# E180-ZG120B-TB-SCH.net
KiCad netlist of a schematic drawn in Altium Designer
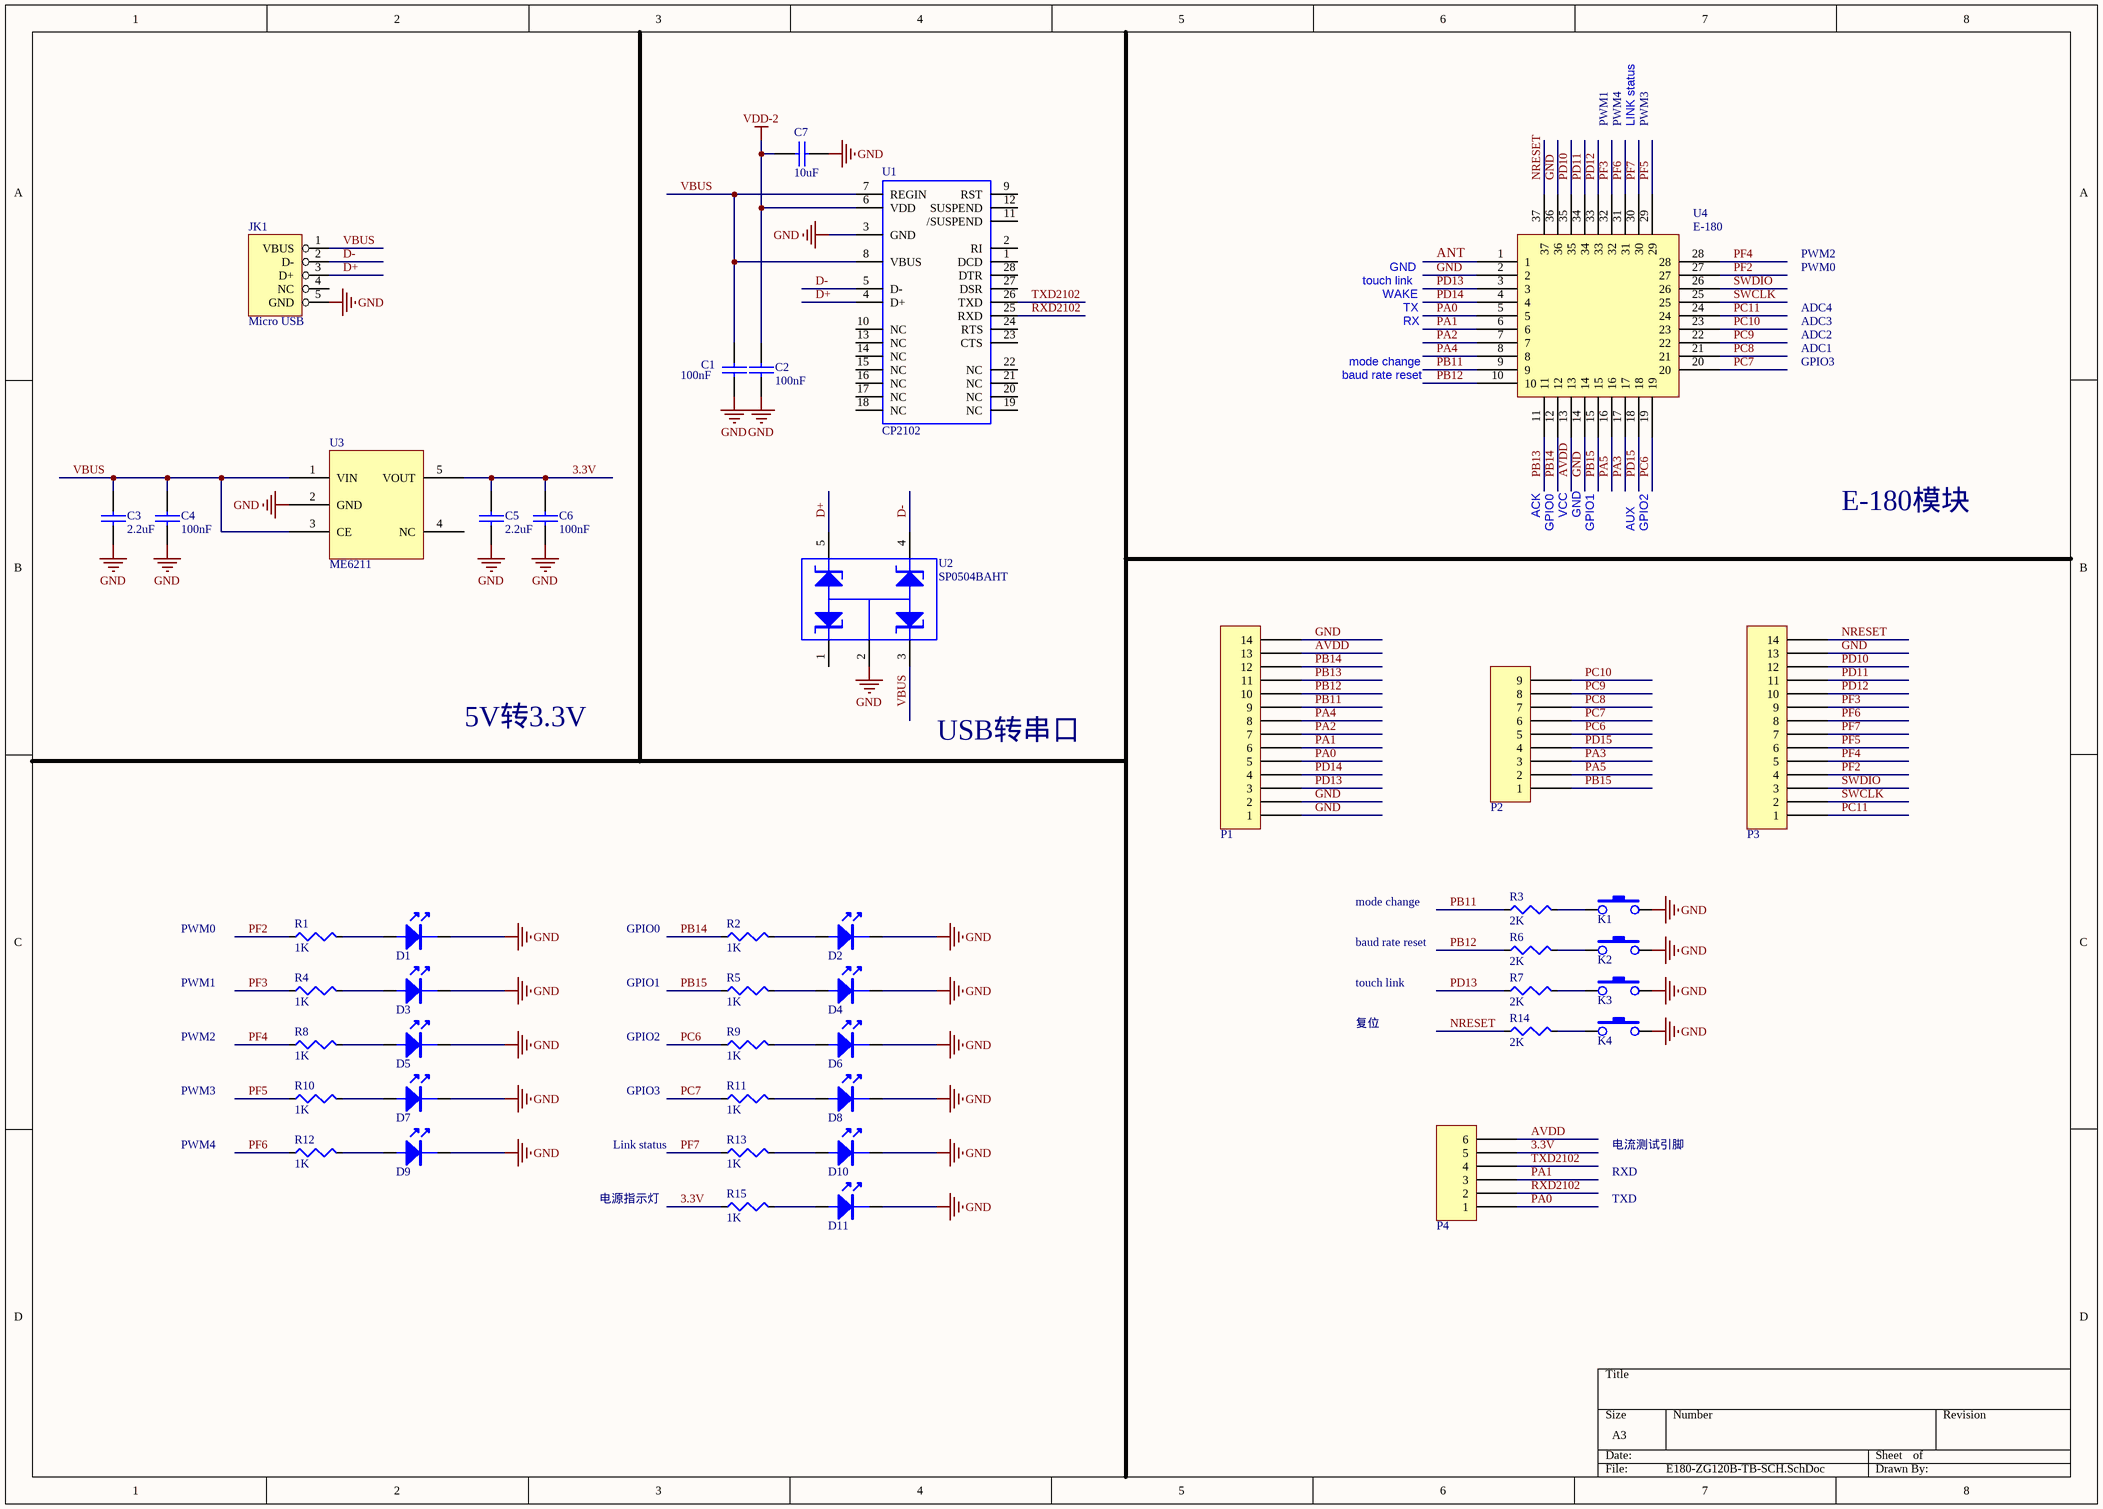
[diagram p0: E180-ZG120B-TB-SCH.SchDoc]

(export (version "E")
  (design (tool "Eeschema 10.0.6"))
  (components
    (comp (ref "C1")
      (value "100nF")
      (footprint "E-CAP-0603")
      (description "Capacitor")
      (libsource (lib "E180-TBB01") (part "CAP 0603"))
    )
    (comp (ref "C2")
      (value "100nF")
      (footprint "E-CAP-0603")
      (description "Capacitor")
      (libsource (lib "E180-TBB01") (part "CAP 0603"))
    )
    (comp (ref "C3")
      (value "2.2uF")
      (footprint "E-CAP-0603")
      (description "Capacitor")
      (libsource (lib "E180-TBB01") (part "CAP 0603"))
    )
    (comp (ref "C4")
      (value "100nF")
      (footprint "E-CAP-0603")
      (description "Capacitor")
      (libsource (lib "E180-TBB01") (part "CAP 0603"))
    )
    (comp (ref "C5")
      (value "2.2uF")
      (footprint "E-CAP-0603")
      (description "Capacitor")
      (libsource (lib "E180-TBB01") (part "CAP 0603"))
    )
    (comp (ref "C6")
      (value "100nF")
      (footprint "E-CAP-0603")
      (description "Capacitor")
      (libsource (lib "E180-TBB01") (part "CAP 0603"))
    )
    (comp (ref "C7")
      (value "10uF")
      (footprint "E-CAP-0603")
      (description "Capacitor")
      (libsource (lib "E180-TBB01") (part "CAP 0603"))
    )
    (comp (ref "D1") (value "LED") (footprint "E-LED-0603") (libsource (lib "E180-TBB01") (part "LED")))
    (comp (ref "D2") (value "LED") (footprint "E-LED-0603") (libsource (lib "E180-TBB01") (part "LED")))
    (comp (ref "D3") (value "LED") (footprint "E-LED-0603") (libsource (lib "E180-TBB01") (part "LED")))
    (comp (ref "D4") (value "LED") (footprint "E-LED-0603") (libsource (lib "E180-TBB01") (part "LED")))
    (comp (ref "D5") (value "LED") (footprint "E-LED-0603") (libsource (lib "E180-TBB01") (part "LED")))
    (comp (ref "D6") (value "LED") (footprint "E-LED-0603") (libsource (lib "E180-TBB01") (part "LED")))
    (comp (ref "D7") (value "LED") (footprint "E-LED-0603") (libsource (lib "E180-TBB01") (part "LED")))
    (comp (ref "D8") (value "LED") (footprint "E-LED-0603") (libsource (lib "E180-TBB01") (part "LED")))
    (comp (ref "D9") (value "LED") (footprint "E-LED-0603") (libsource (lib "E180-TBB01") (part "LED")))
    (comp (ref "D10") (value "LED") (footprint "E-LED-0603") (libsource (lib "E180-TBB01") (part "LED")))
    (comp (ref "D11") (value "LED") (footprint "E-LED-0603") (libsource (lib "E180-TBB01") (part "LED")))
    (comp (ref "JK1")
      (value "Micro USB")
      (footprint "E-Micro USB-5SB")
      (libsource (lib "E180-TBB01") (part "Micro USB"))
    )
    (comp (ref "K1") (value "KEY0") (footprint "KEY") (libsource (lib "E180-TBB01") (part "KEY0")))
    (comp (ref "K2") (value "KEY0") (footprint "KEY") (libsource (lib "E180-TBB01") (part "KEY0")))
    (comp (ref "K3") (value "KEY0") (footprint "KEY") (libsource (lib "E180-TBB01") (part "KEY0")))
    (comp (ref "K4") (value "KEY0") (footprint "KEY") (libsource (lib "E180-TBB01") (part "KEY0")))
    (comp (ref "P1")
      (value "Header1*14")
      (footprint "E-2X7P-2.54-1")
      (libsource (lib "E180-TBB01") (part "Header1*14"))
    )
    (comp (ref "P2")
      (value "Header1*9")
      (footprint "E-9P-2.54-1")
      (libsource (lib "E180-TBB01") (part "Header1*9"))
    )
    (comp (ref "P3")
      (value "Header1*14")
      (footprint "E-2X7P-2.54-1")
      (libsource (lib "E180-TBB01") (part "Header1*14"))
    )
    (comp (ref "P4")
      (value "Header1*6")
      (footprint "E-6P-2.54-1")
      (libsource (lib "E180-TBB01") (part "Header1*6"))
    )
    (comp (ref "R1") (value "1K") (footprint "E-RES-0603") (libsource (lib "E180-TBB01") (part "RES 0603")))
    (comp (ref "R2") (value "1K") (footprint "E-RES-0603") (libsource (lib "E180-TBB01") (part "RES 0603")))
    (comp (ref "R3") (value "2K") (footprint "E-RES-0603") (libsource (lib "E180-TBB01") (part "RES 0603")))
    (comp (ref "R4") (value "1K") (footprint "E-RES-0603") (libsource (lib "E180-TBB01") (part "RES 0603")))
    (comp (ref "R5") (value "1K") (footprint "E-RES-0603") (libsource (lib "E180-TBB01") (part "RES 0603")))
    (comp (ref "R6") (value "2K") (footprint "E-RES-0603") (libsource (lib "E180-TBB01") (part "RES 0603")))
    (comp (ref "R7") (value "2K") (footprint "E-RES-0603") (libsource (lib "E180-TBB01") (part "RES 0603")))
    (comp (ref "R8") (value "1K") (footprint "E-RES-0603") (libsource (lib "E180-TBB01") (part "RES 0603")))
    (comp (ref "R9") (value "1K") (footprint "E-RES-0603") (libsource (lib "E180-TBB01") (part "RES 0603")))
    (comp (ref "R10") (value "1K") (footprint "E-RES-0603") (libsource (lib "E180-TBB01") (part "RES 0603")))
    (comp (ref "R11") (value "1K") (footprint "E-RES-0603") (libsource (lib "E180-TBB01") (part "RES 0603")))
    (comp (ref "R12") (value "1K") (footprint "E-RES-0603") (libsource (lib "E180-TBB01") (part "RES 0603")))
    (comp (ref "R13") (value "1K") (footprint "E-RES-0603") (libsource (lib "E180-TBB01") (part "RES 0603")))
    (comp (ref "R14") (value "2K") (footprint "E-RES-0603") (libsource (lib "E180-TBB01") (part "RES 0603")))
    (comp (ref "R15") (value "1K") (footprint "E-RES-0603") (libsource (lib "E180-TBB01") (part "RES 0603")))
    (comp (ref "U1")
      (value "CP2102")
      (footprint "E-QFN28-5X5-P0.5")
      (libsource (lib "E180-TBB01") (part "CP2102"))
    )
    (comp (ref "U2") (value "SP0504BAHT") (footprint "SP0504") (libsource (lib "E180-TBB01") (part "SP0504")))
    (comp (ref "U3") (value "ME6211") (footprint "E-SOT23-5") (libsource (lib "E180-TBB01") (part "HT7233")))
    (comp (ref "U4") (value "E-180") (footprint "E-180") (libsource (lib "E180-TBB01") (part "E-180")))
  )
  (nets
    (net (code "1") (name "/3.3V") (class "Default")
      (node (ref "C5") (pin "1") (pinfunction "1_1") (pintype "passive"))
      (node (ref "C6") (pin "1") (pinfunction "1_1") (pintype "passive"))
      (node (ref "P4") (pin "5") (pinfunction "5_5") (pintype "passive"))
      (node (ref "R15") (pin "1") (pinfunction "1_1") (pintype "passive"))
      (node (ref "U3") (pin "5") (pinfunction "VOUT_5") (pintype "passive"))
    )
    (net (code "3") (name "/ANT") (class "Default")
      (node (ref "U4") (pin "1") (pinfunction "1_1") (pintype "passive"))
    )
    (net (code "5") (name "/AVDD") (class "Default")
      (node (ref "P1") (pin "13") (pinfunction "13_13") (pintype "passive"))
      (node (ref "P4") (pin "6") (pinfunction "6_6") (pintype "passive"))
      (node (ref "U4") (pin "13") (pinfunction "13_13") (pintype "passive"))
    )
    (net (code "6") (name "/D+") (class "Default")
      (node (ref "JK1") (pin "3") (pinfunction "D+_3") (pintype "passive"))
      (node (ref "U1") (pin "4") (pinfunction "D+_4") (pintype "passive"))
      (node (ref "U2") (pin "5") (pinfunction "5_5") (pintype "passive"))
    )
    (net (code "7") (name "/D-") (class "Default")
      (node (ref "JK1") (pin "2") (pinfunction "D-_2") (pintype "passive"))
      (node (ref "U1") (pin "5") (pinfunction "D-_5") (pintype "passive"))
      (node (ref "U2") (pin "4") (pinfunction "4_4") (pintype "passive"))
    )
    (net (code "12") (name "/NRESET") (class "Default")
      (node (ref "P3") (pin "14") (pinfunction "14_14") (pintype "passive"))
      (node (ref "R14") (pin "1") (pinfunction "1_1") (pintype "passive"))
      (node (ref "U4") (pin "37") (pinfunction "37_37") (pintype "passive"))
    )
    (net (code "13") (name "/PA0") (class "Default")
      (node (ref "P1") (pin "5") (pinfunction "5_5") (pintype "passive"))
      (node (ref "P4") (pin "1") (pinfunction "1_1") (pintype "passive"))
      (node (ref "U4") (pin "5") (pinfunction "5_5") (pintype "passive"))
    )
    (net (code "14") (name "/PA1") (class "Default")
      (node (ref "P1") (pin "6") (pinfunction "6_6") (pintype "passive"))
      (node (ref "P4") (pin "3") (pinfunction "3_3") (pintype "passive"))
      (node (ref "U4") (pin "6") (pinfunction "6_6") (pintype "passive"))
    )
    (net (code "15") (name "/PA2") (class "Default")
      (node (ref "P1") (pin "7") (pinfunction "7_7") (pintype "passive"))
      (node (ref "U4") (pin "7") (pinfunction "7_7") (pintype "passive"))
    )
    (net (code "16") (name "/PA3") (class "Default")
      (node (ref "P2") (pin "3") (pinfunction "3_3") (pintype "passive"))
      (node (ref "U4") (pin "17") (pinfunction "17_17") (pintype "passive"))
    )
    (net (code "17") (name "/PA4") (class "Default")
      (node (ref "P1") (pin "8") (pinfunction "8_8") (pintype "passive"))
      (node (ref "U4") (pin "8") (pinfunction "8_8") (pintype "passive"))
    )
    (net (code "18") (name "/PA5") (class "Default")
      (node (ref "P2") (pin "2") (pinfunction "2_2") (pintype "passive"))
      (node (ref "U4") (pin "16") (pinfunction "16_16") (pintype "passive"))
    )
    (net (code "19") (name "/PB11") (class "Default")
      (node (ref "P1") (pin "9") (pinfunction "9_9") (pintype "passive"))
      (node (ref "R3") (pin "1") (pinfunction "1_1") (pintype "passive"))
      (node (ref "U4") (pin "9") (pinfunction "9_9") (pintype "passive"))
    )
    (net (code "20") (name "/PB12") (class "Default")
      (node (ref "P1") (pin "10") (pinfunction "10_10") (pintype "passive"))
      (node (ref "R6") (pin "1") (pinfunction "1_1") (pintype "passive"))
      (node (ref "U4") (pin "10") (pinfunction "10_10") (pintype "passive"))
    )
    (net (code "21") (name "/PB13") (class "Default")
      (node (ref "P1") (pin "11") (pinfunction "11_11") (pintype "passive"))
      (node (ref "U4") (pin "11") (pinfunction "11_11") (pintype "passive"))
    )
    (net (code "22") (name "/PB14") (class "Default")
      (node (ref "P1") (pin "12") (pinfunction "12_12") (pintype "passive"))
      (node (ref "R2") (pin "1") (pinfunction "1_1") (pintype "passive"))
      (node (ref "U4") (pin "12") (pinfunction "12_12") (pintype "passive"))
    )
    (net (code "23") (name "/PB15") (class "Default")
      (node (ref "P2") (pin "1") (pinfunction "1_1") (pintype "passive"))
      (node (ref "R5") (pin "1") (pinfunction "1_1") (pintype "passive"))
      (node (ref "U4") (pin "15") (pinfunction "15_15") (pintype "passive"))
    )
    (net (code "24") (name "/PC6") (class "Default")
      (node (ref "P2") (pin "5") (pinfunction "5_5") (pintype "passive"))
      (node (ref "R9") (pin "1") (pinfunction "1_1") (pintype "passive"))
      (node (ref "U4") (pin "19") (pinfunction "19_19") (pintype "passive"))
    )
    (net (code "25") (name "/PC7") (class "Default")
      (node (ref "P2") (pin "6") (pinfunction "6_6") (pintype "passive"))
      (node (ref "R11") (pin "1") (pinfunction "1_1") (pintype "passive"))
      (node (ref "U4") (pin "20") (pinfunction "20_20") (pintype "passive"))
    )
    (net (code "26") (name "/PC8") (class "Default")
      (node (ref "P2") (pin "7") (pinfunction "7_7") (pintype "passive"))
      (node (ref "U4") (pin "21") (pinfunction "21_21") (pintype "passive"))
    )
    (net (code "27") (name "/PC9") (class "Default")
      (node (ref "P2") (pin "8") (pinfunction "8_8") (pintype "passive"))
      (node (ref "U4") (pin "22") (pinfunction "22_22") (pintype "passive"))
    )
    (net (code "28") (name "/PC10") (class "Default")
      (node (ref "P2") (pin "9") (pinfunction "9_9") (pintype "passive"))
      (node (ref "U4") (pin "23") (pinfunction "23_23") (pintype "passive"))
    )
    (net (code "29") (name "/PC11") (class "Default")
      (node (ref "P3") (pin "1") (pinfunction "1_1") (pintype "passive"))
      (node (ref "U4") (pin "24") (pinfunction "24_24") (pintype "passive"))
    )
    (net (code "30") (name "/PD10") (class "Default")
      (node (ref "P3") (pin "12") (pinfunction "12_12") (pintype "passive"))
      (node (ref "U4") (pin "35") (pinfunction "35_35") (pintype "passive"))
    )
    (net (code "31") (name "/PD11") (class "Default")
      (node (ref "P3") (pin "11") (pinfunction "11_11") (pintype "passive"))
      (node (ref "U4") (pin "34") (pinfunction "34_34") (pintype "passive"))
    )
    (net (code "32") (name "/PD12") (class "Default")
      (node (ref "P3") (pin "10") (pinfunction "10_10") (pintype "passive"))
      (node (ref "U4") (pin "33") (pinfunction "33_33") (pintype "passive"))
    )
    (net (code "33") (name "/PD13") (class "Default")
      (node (ref "P1") (pin "3") (pinfunction "3_3") (pintype "passive"))
      (node (ref "R7") (pin "1") (pinfunction "1_1") (pintype "passive"))
      (node (ref "U4") (pin "3") (pinfunction "3_3") (pintype "passive"))
    )
    (net (code "34") (name "/PD14") (class "Default")
      (node (ref "P1") (pin "4") (pinfunction "4_4") (pintype "passive"))
      (node (ref "U4") (pin "4") (pinfunction "4_4") (pintype "passive"))
    )
    (net (code "35") (name "/PD15") (class "Default")
      (node (ref "P2") (pin "4") (pinfunction "4_4") (pintype "passive"))
      (node (ref "U4") (pin "18") (pinfunction "18_18") (pintype "passive"))
    )
    (net (code "36") (name "/PF2") (class "Default")
      (node (ref "P3") (pin "4") (pinfunction "4_4") (pintype "passive"))
      (node (ref "R1") (pin "1") (pinfunction "1_1") (pintype "passive"))
      (node (ref "U4") (pin "27") (pinfunction "27_27") (pintype "passive"))
    )
    (net (code "37") (name "/PF3") (class "Default")
      (node (ref "P3") (pin "9") (pinfunction "9_9") (pintype "passive"))
      (node (ref "R4") (pin "1") (pinfunction "1_1") (pintype "passive"))
      (node (ref "U4") (pin "32") (pinfunction "32_32") (pintype "passive"))
    )
    (net (code "38") (name "/PF4") (class "Default")
      (node (ref "P3") (pin "5") (pinfunction "5_5") (pintype "passive"))
      (node (ref "R8") (pin "1") (pinfunction "1_1") (pintype "passive"))
      (node (ref "U4") (pin "28") (pinfunction "28_28") (pintype "passive"))
    )
    (net (code "39") (name "/PF5") (class "Default")
      (node (ref "P3") (pin "6") (pinfunction "6_6") (pintype "passive"))
      (node (ref "R10") (pin "1") (pinfunction "1_1") (pintype "passive"))
      (node (ref "U4") (pin "29") (pinfunction "29_29") (pintype "passive"))
    )
    (net (code "40") (name "/PF6") (class "Default")
      (node (ref "P3") (pin "8") (pinfunction "8_8") (pintype "passive"))
      (node (ref "R12") (pin "1") (pinfunction "1_1") (pintype "passive"))
      (node (ref "U4") (pin "31") (pinfunction "31_31") (pintype "passive"))
    )
    (net (code "41") (name "/PF7") (class "Default")
      (node (ref "P3") (pin "7") (pinfunction "7_7") (pintype "passive"))
      (node (ref "R13") (pin "1") (pinfunction "1_1") (pintype "passive"))
      (node (ref "U4") (pin "30") (pinfunction "30_30") (pintype "passive"))
    )
    (net (code "43") (name "/RXD2102") (class "Default")
      (node (ref "P4") (pin "2") (pinfunction "2_2") (pintype "passive"))
      (node (ref "U1") (pin "25") (pinfunction "RXD_25") (pintype "passive"))
    )
    (net (code "44") (name "/SWCLK") (class "Default")
      (node (ref "P3") (pin "2") (pinfunction "2_2") (pintype "passive"))
      (node (ref "U4") (pin "25") (pinfunction "25_25") (pintype "passive"))
    )
    (net (code "45") (name "/SWDIO") (class "Default")
      (node (ref "P3") (pin "3") (pinfunction "3_3") (pintype "passive"))
      (node (ref "U4") (pin "26") (pinfunction "26_26") (pintype "passive"))
    )
    (net (code "47") (name "/TXD2102") (class "Default")
      (node (ref "P4") (pin "4") (pinfunction "4_4") (pintype "passive"))
      (node (ref "U1") (pin "26") (pinfunction "TXD_26") (pintype "passive"))
    )
    (net (code "48") (name "/VBUS") (class "Default")
      (node (ref "C1") (pin "1") (pinfunction "1_1") (pintype "passive"))
      (node (ref "C3") (pin "1") (pinfunction "1_1") (pintype "passive"))
      (node (ref "C4") (pin "1") (pinfunction "1_1") (pintype "passive"))
      (node (ref "JK1") (pin "1") (pinfunction "VBUS_1") (pintype "passive"))
      (node (ref "U1") (pin "7") (pinfunction "REGIN_7") (pintype "passive"))
      (node (ref "U1") (pin "8") (pinfunction "VBUS_8") (pintype "passive"))
      (node (ref "U2") (pin "3") (pinfunction "3_3") (pintype "passive"))
      (node (ref "U3") (pin "1") (pinfunction "VIN_1") (pintype "passive"))
      (node (ref "U3") (pin "3") (pinfunction "CE_3") (pintype "passive"))
    )
    (net (code "54") (name "GND") (class "Default")
      (node (ref "C1") (pin "2") (pinfunction "2_2") (pintype "passive"))
      (node (ref "C2") (pin "2") (pinfunction "2_2") (pintype "passive"))
      (node (ref "C3") (pin "2") (pinfunction "2_2") (pintype "passive"))
      (node (ref "C4") (pin "2") (pinfunction "2_2") (pintype "passive"))
      (node (ref "C5") (pin "2") (pinfunction "2_2") (pintype "passive"))
      (node (ref "C6") (pin "2") (pinfunction "2_2") (pintype "passive"))
      (node (ref "C7") (pin "2") (pinfunction "2_2") (pintype "passive"))
      (node (ref "D1") (pin "K") (pinfunction "K_K") (pintype "passive"))
      (node (ref "D10") (pin "K") (pinfunction "K_K") (pintype "passive"))
      (node (ref "D11") (pin "K") (pinfunction "K_K") (pintype "passive"))
      (node (ref "D2") (pin "K") (pinfunction "K_K") (pintype "passive"))
      (node (ref "D3") (pin "K") (pinfunction "K_K") (pintype "passive"))
      (node (ref "D4") (pin "K") (pinfunction "K_K") (pintype "passive"))
      (node (ref "D5") (pin "K") (pinfunction "K_K") (pintype "passive"))
      (node (ref "D6") (pin "K") (pinfunction "K_K") (pintype "passive"))
      (node (ref "D7") (pin "K") (pinfunction "K_K") (pintype "passive"))
      (node (ref "D8") (pin "K") (pinfunction "K_K") (pintype "passive"))
      (node (ref "D9") (pin "K") (pinfunction "K_K") (pintype "passive"))
      (node (ref "JK1") (pin "5") (pinfunction "GND_5") (pintype "passive"))
      (node (ref "K1") (pin "2") (pinfunction "2_2") (pintype "passive"))
      (node (ref "K2") (pin "2") (pinfunction "2_2") (pintype "passive"))
      (node (ref "K3") (pin "2") (pinfunction "2_2") (pintype "passive"))
      (node (ref "K4") (pin "2") (pinfunction "2_2") (pintype "passive"))
      (node (ref "P1") (pin "1") (pinfunction "1_1") (pintype "passive"))
      (node (ref "P1") (pin "14") (pinfunction "14_14") (pintype "passive"))
      (node (ref "P1") (pin "2") (pinfunction "2_2") (pintype "passive"))
      (node (ref "P3") (pin "13") (pinfunction "13_13") (pintype "passive"))
      (node (ref "U1") (pin "3") (pinfunction "GND_3") (pintype "passive"))
      (node (ref "U2") (pin "2") (pinfunction "2_2") (pintype "passive"))
      (node (ref "U3") (pin "2") (pinfunction "GND_2") (pintype "passive"))
      (node (ref "U4") (pin "14") (pinfunction "14_14") (pintype "passive"))
      (node (ref "U4") (pin "2") (pinfunction "2_2") (pintype "passive"))
      (node (ref "U4") (pin "36") (pinfunction "36_36") (pintype "passive"))
    )
    (net (code "55") (name "Net-(D1-PadA)") (class "Default")
      (node (ref "D1") (pin "A") (pinfunction "A_A") (pintype "passive"))
      (node (ref "R1") (pin "2") (pinfunction "2_2") (pintype "passive"))
    )
    (net (code "56") (name "Net-(D2-PadA)") (class "Default")
      (node (ref "D2") (pin "A") (pinfunction "A_A") (pintype "passive"))
      (node (ref "R2") (pin "2") (pinfunction "2_2") (pintype "passive"))
    )
    (net (code "57") (name "Net-(D3-PadA)") (class "Default")
      (node (ref "D3") (pin "A") (pinfunction "A_A") (pintype "passive"))
      (node (ref "R4") (pin "2") (pinfunction "2_2") (pintype "passive"))
    )
    (net (code "58") (name "Net-(D4-PadA)") (class "Default")
      (node (ref "D4") (pin "A") (pinfunction "A_A") (pintype "passive"))
      (node (ref "R5") (pin "2") (pinfunction "2_2") (pintype "passive"))
    )
    (net (code "59") (name "Net-(D5-PadA)") (class "Default")
      (node (ref "D5") (pin "A") (pinfunction "A_A") (pintype "passive"))
      (node (ref "R8") (pin "2") (pinfunction "2_2") (pintype "passive"))
    )
    (net (code "60") (name "Net-(D6-PadA)") (class "Default")
      (node (ref "D6") (pin "A") (pinfunction "A_A") (pintype "passive"))
      (node (ref "R9") (pin "2") (pinfunction "2_2") (pintype "passive"))
    )
    (net (code "61") (name "Net-(D7-PadA)") (class "Default")
      (node (ref "D7") (pin "A") (pinfunction "A_A") (pintype "passive"))
      (node (ref "R10") (pin "2") (pinfunction "2_2") (pintype "passive"))
    )
    (net (code "62") (name "Net-(D8-PadA)") (class "Default")
      (node (ref "D8") (pin "A") (pinfunction "A_A") (pintype "passive"))
      (node (ref "R11") (pin "2") (pinfunction "2_2") (pintype "passive"))
    )
    (net (code "63") (name "Net-(D9-PadA)") (class "Default")
      (node (ref "D9") (pin "A") (pinfunction "A_A") (pintype "passive"))
      (node (ref "R12") (pin "2") (pinfunction "2_2") (pintype "passive"))
    )
    (net (code "64") (name "Net-(D10-PadA)") (class "Default")
      (node (ref "D10") (pin "A") (pinfunction "A_A") (pintype "passive"))
      (node (ref "R13") (pin "2") (pinfunction "2_2") (pintype "passive"))
    )
    (net (code "65") (name "Net-(D11-PadA)") (class "Default")
      (node (ref "D11") (pin "A") (pinfunction "A_A") (pintype "passive"))
      (node (ref "R15") (pin "2") (pinfunction "2_2") (pintype "passive"))
    )
    (net (code "66") (name "Net-(K1-Pad1)") (class "Default")
      (node (ref "K1") (pin "1") (pinfunction "1_1") (pintype "passive"))
      (node (ref "R3") (pin "2") (pinfunction "2_2") (pintype "passive"))
    )
    (net (code "67") (name "Net-(K2-Pad1)") (class "Default")
      (node (ref "K2") (pin "1") (pinfunction "1_1") (pintype "passive"))
      (node (ref "R6") (pin "2") (pinfunction "2_2") (pintype "passive"))
    )
    (net (code "68") (name "Net-(K3-Pad1)") (class "Default")
      (node (ref "K3") (pin "1") (pinfunction "1_1") (pintype "passive"))
      (node (ref "R7") (pin "2") (pinfunction "2_2") (pintype "passive"))
    )
    (net (code "69") (name "Net-(K4-Pad1)") (class "Default")
      (node (ref "K4") (pin "1") (pinfunction "1_1") (pintype "passive"))
      (node (ref "R14") (pin "2") (pinfunction "2_2") (pintype "passive"))
    )
    (net (code "70") (name "VDD-2") (class "Default")
      (node (ref "C2") (pin "1") (pinfunction "1_1") (pintype "passive"))
      (node (ref "C7") (pin "1") (pinfunction "1_1") (pintype "passive"))
      (node (ref "U1") (pin "6") (pinfunction "VDD_6") (pintype "passive"))
    )
    (net (code "71") (name "unconnected-(JK1-NC-Pad4)") (class "Default")
      (node (ref "JK1") (pin "4") (pinfunction "NC_4") (pintype "passive"))
    )
    (net (code "72") (name "unconnected-(U1-CTS-Pad23)") (class "Default")
      (node (ref "U1") (pin "23") (pinfunction "CTS_23") (pintype "passive"))
    )
    (net (code "73") (name "unconnected-(U1-DCD-Pad1)") (class "Default")
      (node (ref "U1") (pin "1") (pinfunction "DCD_1") (pintype "passive"))
    )
    (net (code "74") (name "unconnected-(U1-DSR-Pad27)") (class "Default")
      (node (ref "U1") (pin "27") (pinfunction "DSR_27") (pintype "passive"))
    )
    (net (code "75") (name "unconnected-(U1-DTR-Pad28)") (class "Default")
      (node (ref "U1") (pin "28") (pinfunction "DTR_28") (pintype "passive"))
    )
    (net (code "76") (name "unconnected-(U1-NC-Pad10)") (class "Default")
      (node (ref "U1") (pin "10") (pinfunction "NC_10") (pintype "passive"))
    )
    (net (code "77") (name "unconnected-(U1-NC-Pad13)") (class "Default")
      (node (ref "U1") (pin "13") (pinfunction "NC_13") (pintype "passive"))
    )
    (net (code "78") (name "unconnected-(U1-NC-Pad14)") (class "Default")
      (node (ref "U1") (pin "14") (pinfunction "NC_14") (pintype "passive"))
    )
    (net (code "79") (name "unconnected-(U1-NC-Pad15)") (class "Default")
      (node (ref "U1") (pin "15") (pinfunction "NC_15") (pintype "passive"))
    )
    (net (code "80") (name "unconnected-(U1-NC-Pad16)") (class "Default")
      (node (ref "U1") (pin "16") (pinfunction "NC_16") (pintype "passive"))
    )
    (net (code "81") (name "unconnected-(U1-NC-Pad17)") (class "Default")
      (node (ref "U1") (pin "17") (pinfunction "NC_17") (pintype "passive"))
    )
    (net (code "82") (name "unconnected-(U1-NC-Pad18)") (class "Default")
      (node (ref "U1") (pin "18") (pinfunction "NC_18") (pintype "passive"))
    )
    (net (code "83") (name "unconnected-(U1-NC-Pad19)") (class "Default")
      (node (ref "U1") (pin "19") (pinfunction "NC_19") (pintype "passive"))
    )
    (net (code "84") (name "unconnected-(U1-NC-Pad20)") (class "Default")
      (node (ref "U1") (pin "20") (pinfunction "NC_20") (pintype "passive"))
    )
    (net (code "85") (name "unconnected-(U1-NC-Pad21)") (class "Default")
      (node (ref "U1") (pin "21") (pinfunction "NC_21") (pintype "passive"))
    )
    (net (code "86") (name "unconnected-(U1-NC-Pad22)") (class "Default")
      (node (ref "U1") (pin "22") (pinfunction "NC_22") (pintype "passive"))
    )
    (net (code "87") (name "unconnected-(U1-RI-Pad2)") (class "Default")
      (node (ref "U1") (pin "2") (pinfunction "RI_2") (pintype "passive"))
    )
    (net (code "88") (name "unconnected-(U1-RST-Pad9)") (class "Default")
      (node (ref "U1") (pin "9") (pinfunction "RST_9") (pintype "passive"))
    )
    (net (code "89") (name "unconnected-(U1-RTS-Pad24)") (class "Default")
      (node (ref "U1") (pin "24") (pinfunction "RTS_24") (pintype "passive"))
    )
    (net (code "90") (name "unconnected-(U1-SUSPEND-Pad12)") (class "Default")
      (node (ref "U1") (pin "12") (pinfunction "SUSPEND_12") (pintype "passive"))
    )
    (net (code "91") (name "unconnected-(U1-{slash}SUSPEND-Pad11)") (class "Default")
      (node (ref "U1") (pin "11") (pinfunction "/SUSPEND_11") (pintype "passive"))
    )
    (net (code "92") (name "unconnected-(U2-Pad1)") (class "Default")
      (node (ref "U2") (pin "1") (pinfunction "1_1") (pintype "passive"))
    )
    (net (code "93") (name "unconnected-(U3-NC-Pad4)") (class "Default")
      (node (ref "U3") (pin "4") (pinfunction "NC_4") (pintype "passive"))
    )
  )
)
